# CW_KEY_EXTENSION.net
KiCad netlist of a schematic drawn in EAGLE
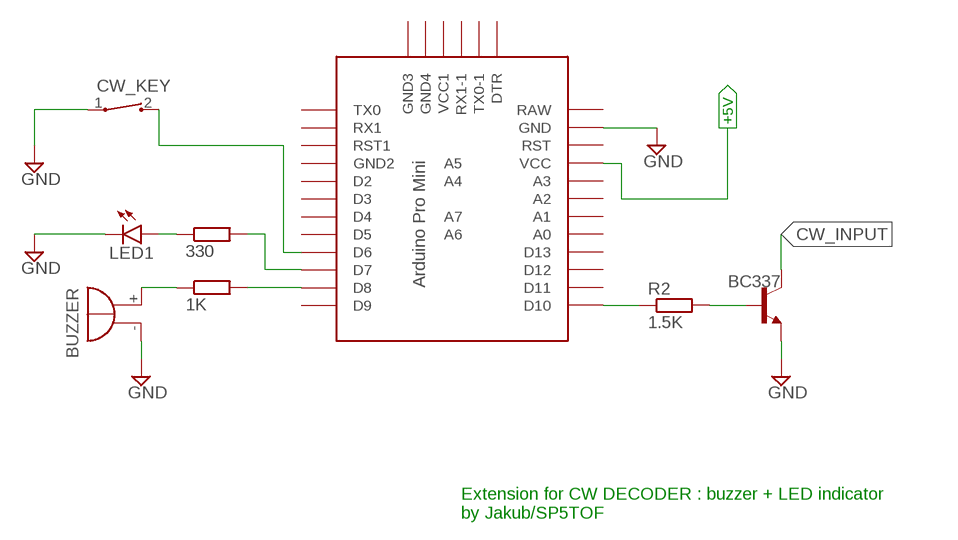
[diagram p0: schematic, sheet 1]

(export (version "E")
  (design (tool "Eeschema 10.0.6"))
  (components
    (comp (ref "BUZZER")
      (value "EB2209A")
      (footprint "eagle-import:EB2209A")
      (libsource (lib "eagle-import") (part "EB2209A"))
    )
    (comp (ref "CW_KEY")
      (value "CT10-XXXX-A2")
      (footprint "eagle-import:CT10-XXXX-A2")
      (libsource (lib "eagle-import") (part "CT10-XXXX-A2"))
    )
    (comp (ref "LED1")
      (value "LAP4-BOTTOM")
      (footprint "eagle-import:P47F-BOTTOM")
      (libsource (lib "eagle-import") (part "P4-BOTTOMLA"))
    )
    (comp (ref "R1")
      (value "330")
      (footprint "eagle-import:0204_5")
      (libsource (lib "eagle-import") (part "R-EU_0204/5"))
    )
    (comp (ref "R2")
      (value "1.5K")
      (footprint "eagle-import:0204_5")
      (libsource (lib "eagle-import") (part "R-EU_0204/5"))
    )
    (comp (ref "R3")
      (value "1K")
      (footprint "eagle-import:0204_5")
      (libsource (lib "eagle-import") (part "R-EU_0204/5"))
    )
    (comp (ref "T1")
      (value "BC337")
      (footprint "eagle-import:TO92")
      (libsource (lib "eagle-import") (part "BC337"))
    )
    (comp (ref "U$1")
      (value "PRO-MINI-2")
      (footprint "eagle-import:PRO-MINI-2")
      (libsource (lib "eagle-import") (part "PRO-MINI-2"))
    )
  )
  (nets
    (net (code "1") (name "+5V") (class "Default")
      (node (ref "U$1") (pin "VCC") (pinfunction "VCC_VCC") (pintype "bidirectional"))
    )
    (net (code "2") (name "CW_INPUT") (class "Default")
      (node (ref "T1") (pin "3") (pinfunction "C_3") (pintype "passive"))
    )
    (net (code "3") (name "GND") (class "Default")
      (node (ref "BUZZER") (pin "-") (pinfunction "-_-") (pintype "passive"))
      (node (ref "CW_KEY") (pin "1") (pinfunction "1_1") (pintype "passive"))
      (node (ref "LED1") (pin "C") (pinfunction "C_C") (pintype "passive"))
      (node (ref "T1") (pin "1") (pinfunction "E_1") (pintype "passive"))
      (node (ref "U$1") (pin "GND") (pinfunction "GND_GND") (pintype "bidirectional"))
    )
    (net (code "4") (name "Net-(BUZZER-Pad+)") (class "Default")
      (node (ref "BUZZER") (pin "+") (pinfunction "+_+") (pintype "passive"))
      (node (ref "R3") (pin "1") (pinfunction "1_1") (pintype "passive"))
    )
    (net (code "5") (name "Net-(CW_KEY-Pad2)") (class "Default")
      (node (ref "CW_KEY") (pin "2") (pinfunction "2_2") (pintype "passive"))
      (node (ref "U$1") (pin "D6") (pinfunction "D6_D6") (pintype "bidirectional"))
    )
    (net (code "6") (name "Net-(LED1-PadA)") (class "Default")
      (node (ref "LED1") (pin "A") (pinfunction "A_A") (pintype "passive"))
      (node (ref "R1") (pin "1") (pinfunction "1_1") (pintype "passive"))
    )
    (net (code "7") (name "Net-(R1-Pad2)") (class "Default")
      (node (ref "R1") (pin "2") (pinfunction "2_2") (pintype "passive"))
      (node (ref "U$1") (pin "D7") (pinfunction "D7_D7") (pintype "bidirectional"))
    )
    (net (code "8") (name "Net-(R2-Pad1)") (class "Default")
      (node (ref "R2") (pin "1") (pinfunction "1_1") (pintype "passive"))
      (node (ref "U$1") (pin "D10") (pinfunction "D10_D10") (pintype "bidirectional"))
    )
    (net (code "9") (name "Net-(R3-Pad2)") (class "Default")
      (node (ref "R3") (pin "2") (pinfunction "2_2") (pintype "passive"))
      (node (ref "U$1") (pin "D8") (pinfunction "D8_D8") (pintype "bidirectional"))
    )
    (net (code "10") (name "Net-(T1-B)") (class "Default")
      (node (ref "R2") (pin "2") (pinfunction "2_2") (pintype "passive"))
      (node (ref "T1") (pin "2") (pinfunction "B_2") (pintype "passive"))
    )
    (net (code "11") (name "unconnected-(U$1-GND2-PadGND1)") (class "Default")
      (node (ref "U$1") (pin "GND1") (pinfunction "GND2_GND1") (pintype "bidirectional"))
    )
    (net (code "12") (name "unconnected-(U$1-GND3-PadGND2)") (class "Default")
      (node (ref "U$1") (pin "GND2") (pinfunction "GND3_GND2") (pintype "bidirectional"))
    )
    (net (code "13") (name "unconnected-(U$1-GND4-PadGND3)") (class "Default")
      (node (ref "U$1") (pin "GND3") (pinfunction "GND4_GND3") (pintype "bidirectional"))
    )
    (net (code "14") (name "unconnected-(U$1-PadA0)") (class "Default")
      (node (ref "U$1") (pin "A0") (pinfunction "A0_A0") (pintype "bidirectional"))
    )
    (net (code "15") (name "unconnected-(U$1-PadA1)") (class "Default")
      (node (ref "U$1") (pin "A1") (pinfunction "A1_A1") (pintype "bidirectional"))
    )
    (net (code "16") (name "unconnected-(U$1-PadA2)") (class "Default")
      (node (ref "U$1") (pin "A2") (pinfunction "A2_A2") (pintype "bidirectional"))
    )
    (net (code "17") (name "unconnected-(U$1-PadA3)") (class "Default")
      (node (ref "U$1") (pin "A3") (pinfunction "A3_A3") (pintype "bidirectional"))
    )
    (net (code "18") (name "unconnected-(U$1-PadA4)") (class "Default")
      (node (ref "U$1") (pin "A4") (pinfunction "A4_A4") (pintype "bidirectional"))
    )
    (net (code "19") (name "unconnected-(U$1-PadA5)") (class "Default")
      (node (ref "U$1") (pin "A5") (pinfunction "A5_A5") (pintype "bidirectional"))
    )
    (net (code "20") (name "unconnected-(U$1-PadA6)") (class "Default")
      (node (ref "U$1") (pin "A6") (pinfunction "A6_A6") (pintype "bidirectional"))
    )
    (net (code "21") (name "unconnected-(U$1-PadA7)") (class "Default")
      (node (ref "U$1") (pin "A7") (pinfunction "A7_A7") (pintype "bidirectional"))
    )
    (net (code "22") (name "unconnected-(U$1-PadD2)") (class "Default")
      (node (ref "U$1") (pin "D2") (pinfunction "D2_D2") (pintype "bidirectional"))
    )
    (net (code "23") (name "unconnected-(U$1-PadD3)") (class "Default")
      (node (ref "U$1") (pin "D3") (pinfunction "D3_D3") (pintype "bidirectional"))
    )
    (net (code "24") (name "unconnected-(U$1-PadD4)") (class "Default")
      (node (ref "U$1") (pin "D4") (pinfunction "D4_D4") (pintype "bidirectional"))
    )
    (net (code "25") (name "unconnected-(U$1-PadD5)") (class "Default")
      (node (ref "U$1") (pin "D5") (pinfunction "D5_D5") (pintype "bidirectional"))
    )
    (net (code "26") (name "unconnected-(U$1-PadD9)") (class "Default")
      (node (ref "U$1") (pin "D9") (pinfunction "D9_D9") (pintype "bidirectional"))
    )
    (net (code "27") (name "unconnected-(U$1-PadD11)") (class "Default")
      (node (ref "U$1") (pin "D11") (pinfunction "D11_D11") (pintype "bidirectional"))
    )
    (net (code "28") (name "unconnected-(U$1-PadD12)") (class "Default")
      (node (ref "U$1") (pin "D12") (pinfunction "D12_D12") (pintype "bidirectional"))
    )
    (net (code "29") (name "unconnected-(U$1-PadD13)") (class "Default")
      (node (ref "U$1") (pin "D13") (pinfunction "D13_D13") (pintype "bidirectional"))
    )
    (net (code "30") (name "unconnected-(U$1-PadDTR)") (class "Default")
      (node (ref "U$1") (pin "DTR") (pinfunction "DTR_DTR") (pintype "bidirectional"))
    )
    (net (code "31") (name "unconnected-(U$1-PadRAW)") (class "Default")
      (node (ref "U$1") (pin "RAW") (pinfunction "RAW_RAW") (pintype "bidirectional"))
    )
    (net (code "32") (name "unconnected-(U$1-PadRST)") (class "Default")
      (node (ref "U$1") (pin "RST") (pinfunction "RST_RST") (pintype "bidirectional"))
    )
    (net (code "33") (name "unconnected-(U$1-PadRST1)") (class "Default")
      (node (ref "U$1") (pin "RST1") (pinfunction "RST1_RST1") (pintype "bidirectional"))
    )
    (net (code "34") (name "unconnected-(U$1-PadRX1)") (class "Default")
      (node (ref "U$1") (pin "RX1") (pinfunction "RX1_RX1") (pintype "bidirectional"))
    )
    (net (code "35") (name "unconnected-(U$1-PadRX1-1)") (class "Default")
      (node (ref "U$1") (pin "RX1-1") (pinfunction "RX1-1_RX1-1") (pintype "bidirectional"))
    )
    (net (code "36") (name "unconnected-(U$1-PadTX0)") (class "Default")
      (node (ref "U$1") (pin "TX0") (pinfunction "TX0_TX0") (pintype "bidirectional"))
    )
    (net (code "37") (name "unconnected-(U$1-PadTX0-1)") (class "Default")
      (node (ref "U$1") (pin "TX0-1") (pinfunction "TX0-1_TX0-1") (pintype "bidirectional"))
    )
    (net (code "38") (name "unconnected-(U$1-PadVCC1)") (class "Default")
      (node (ref "U$1") (pin "VCC1") (pinfunction "VCC1_VCC1") (pintype "bidirectional"))
    )
  )
)
